# Propeller-HAT.net
KiCad netlist of a schematic drawn in EAGLE
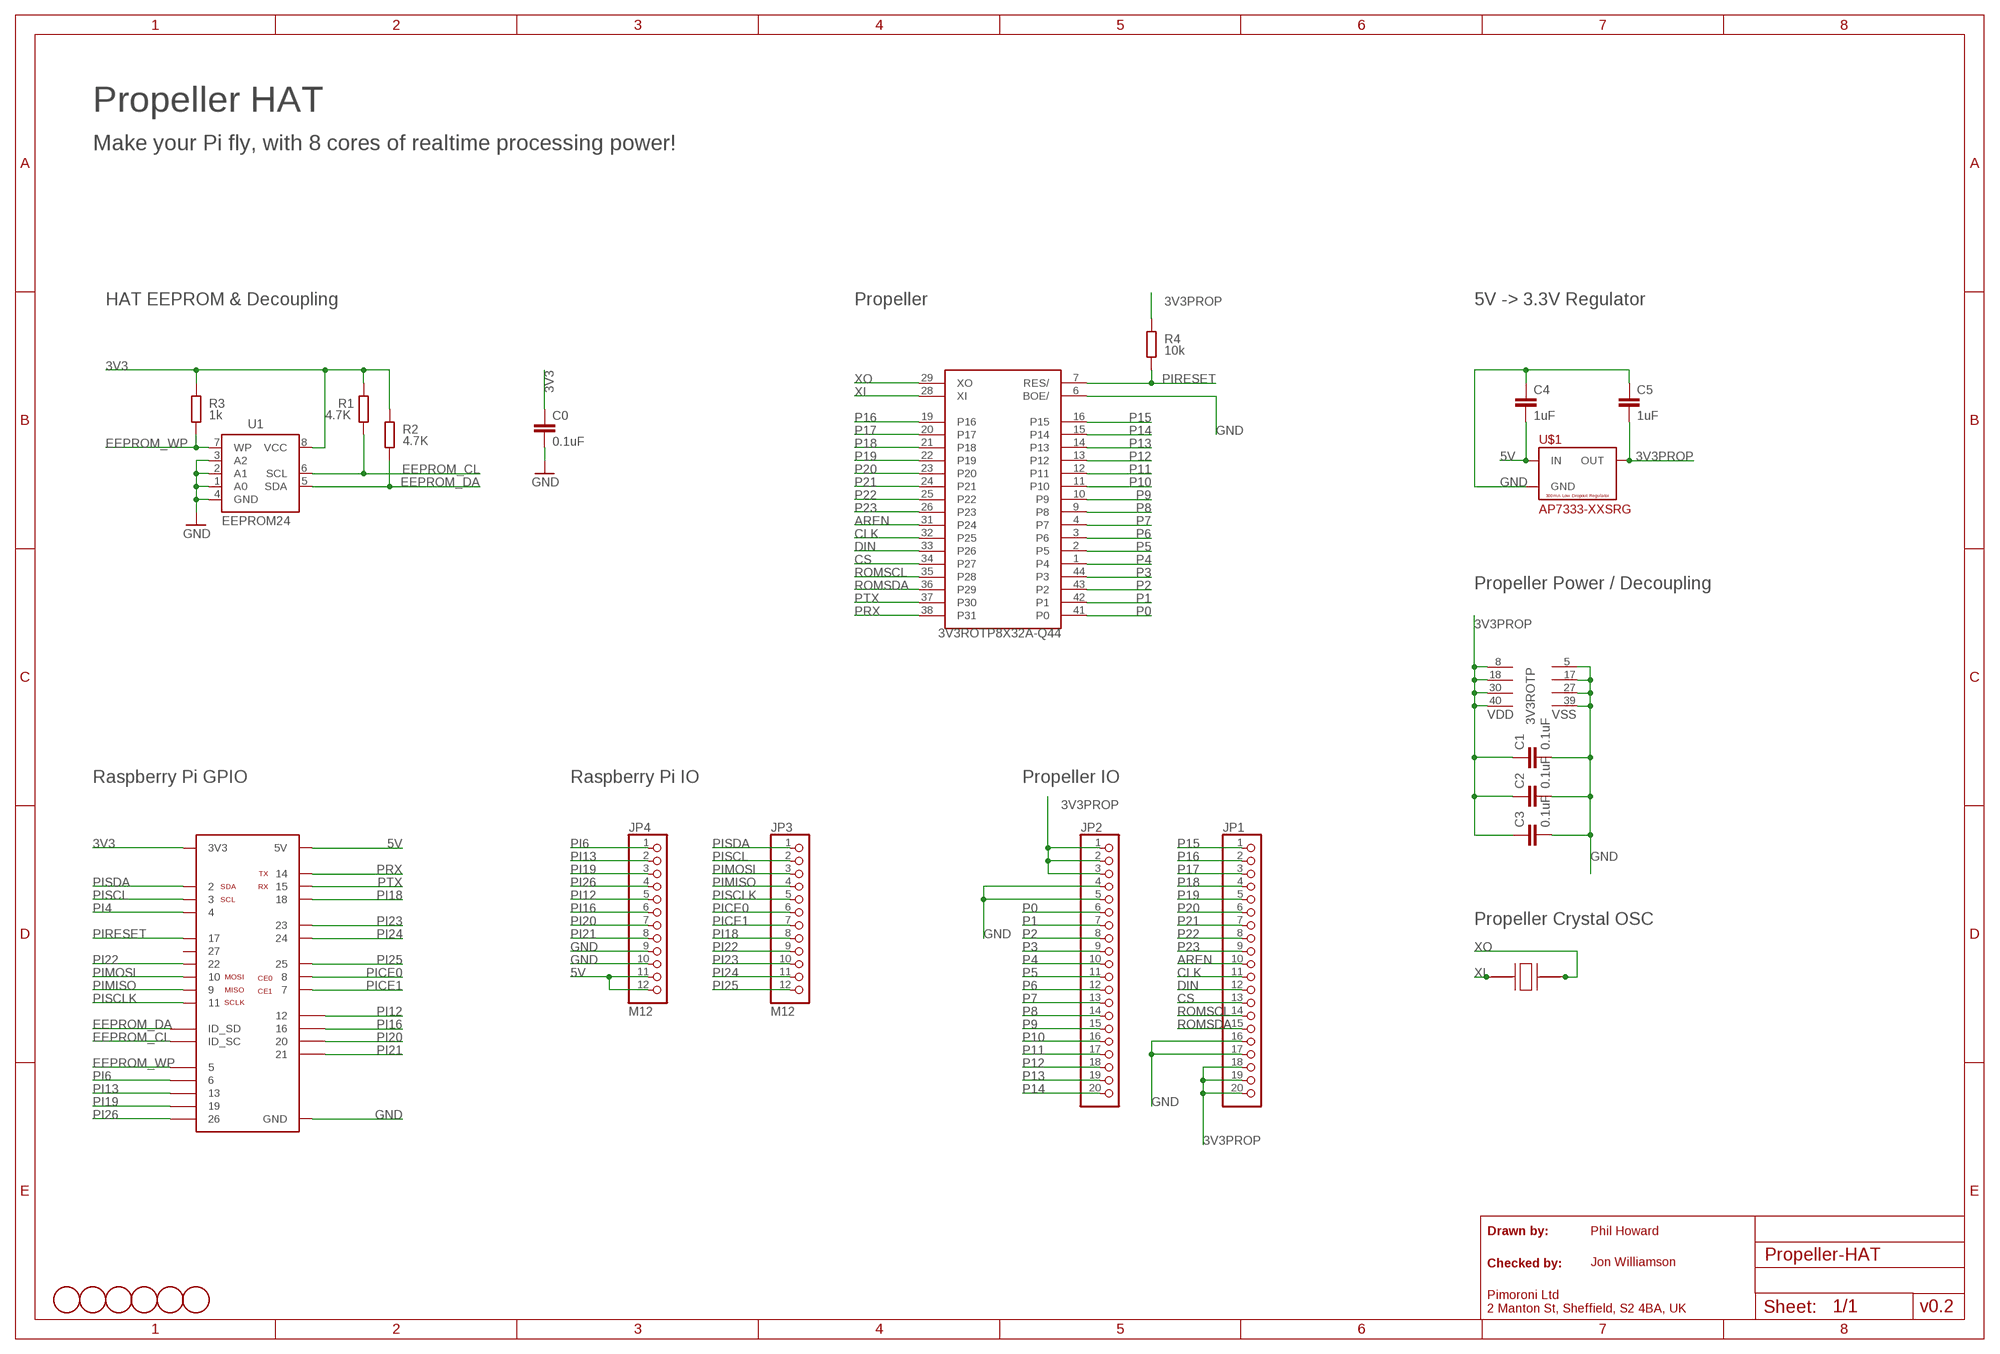
[diagram p0: schematic, sheet 1]

(export (version "E")
  (design (tool "Eeschema 10.0.6"))
  (components
    (comp (ref "3V3ROT")
      (value "P8X32A-Q44")
      (footprint "eagle-import:P8X32A-Q44")
      (libsource (lib "eagle-import") (part "P8X32A-Q44"))
    )
    (comp (ref "C0")
      (value "0.1uF")
      (footprint "eagle-import:C0603K")
      (libsource (lib "eagle-import") (part "C-EUC0603K"))
    )
    (comp (ref "C1")
      (value "0.1uF")
      (footprint "eagle-import:C0603K")
      (libsource (lib "eagle-import") (part "C-EUC0603K"))
    )
    (comp (ref "C2")
      (value "0.1uF")
      (footprint "eagle-import:C0603K")
      (libsource (lib "eagle-import") (part "C-EUC0603K"))
    )
    (comp (ref "C3")
      (value "0.1uF")
      (footprint "eagle-import:C0603K")
      (libsource (lib "eagle-import") (part "C-EUC0603K"))
    )
    (comp (ref "C4")
      (value "1uF")
      (footprint "eagle-import:C0603K")
      (libsource (lib "eagle-import") (part "C-EUC0603K"))
    )
    (comp (ref "C5")
      (value "1uF")
      (footprint "eagle-import:C0603K")
      (libsource (lib "eagle-import") (part "C-EUC0603K"))
    )
    (comp (ref "JP1")
      (value "PINHD-1X20-BIG")
      (footprint "eagle-import:1X20-BIG")
      (libsource (lib "eagle-import") (part "PINHD-1X20-BIG"))
    )
    (comp (ref "JP2")
      (value "PINHD-1X20-BIG")
      (footprint "eagle-import:1X20-BIG")
      (libsource (lib "eagle-import") (part "PINHD-1X20-BIG"))
    )
    (comp (ref "JP3")
      (value "M12")
      (footprint "eagle-import:M12")
      (libsource (lib "eagle-import") (part "M12"))
    )
    (comp (ref "JP4")
      (value "M12")
      (footprint "eagle-import:M12")
      (libsource (lib "eagle-import") (part "M12"))
    )
    (comp (ref "R1")
      (value "4.7K")
      (footprint "eagle-import:R0603")
      (fields (field (name "TOLERANCE") "5%"))
      (libsource (lib "eagle-import") (part "R-EU_R0603"))
    )
    (comp (ref "R2")
      (value "4.7K")
      (footprint "eagle-import:R0603")
      (fields (field (name "TOLERANCE") "5%"))
      (libsource (lib "eagle-import") (part "R-EU_R0603"))
    )
    (comp (ref "R3")
      (value "1k")
      (footprint "eagle-import:R0603")
      (fields (field (name "TOLERANCE") "5%"))
      (libsource (lib "eagle-import") (part "R-EU_R0603"))
    )
    (comp (ref "R4")
      (value "10k")
      (footprint "eagle-import:R0603")
      (fields (field (name "TOLERANCE") "5%"))
      (libsource (lib "eagle-import") (part "R-EU_R0603"))
    )
    (comp (ref "U$1")
      (value "AP7333-XXSRG")
      (footprint "eagle-import:SOT23")
      (libsource (lib "eagle-import") (part "AP7333-XXSRG"))
    )
    (comp (ref "U$2")
      (value "RPIGPIOPINHD-2X20-SMD-FLIPPED")
      (footprint "eagle-import:FCI_89898_313LF_40P_CONNECTOR_SMT_FLIPPED")
      (libsource (lib "eagle-import") (part "RPIGPIOPINHD-2X20-SMD-FLIPPED"))
    )
    (comp (ref "U$3")
      (value "FIDUCIAL1MM")
      (footprint "eagle-import:FIDUCIAL-1MM")
      (libsource (lib "eagle-import") (part "FIDUCIAL1MM"))
    )
    (comp (ref "U$4")
      (value "FIDUCIAL1MM")
      (footprint "eagle-import:FIDUCIAL-1MM")
      (libsource (lib "eagle-import") (part "FIDUCIAL1MM"))
    )
    (comp (ref "U$5")
      (value "FIDUCIAL1MM")
      (footprint "eagle-import:FIDUCIAL-1MM")
      (libsource (lib "eagle-import") (part "FIDUCIAL1MM"))
    )
    (comp (ref "U$6")
      (value "FIDUCIAL1MM")
      (footprint "eagle-import:FIDUCIAL-1MM")
      (libsource (lib "eagle-import") (part "FIDUCIAL1MM"))
    )
    (comp (ref "U$7")
      (value "FIDUCIAL1MM")
      (footprint "eagle-import:FIDUCIAL-1MM")
      (libsource (lib "eagle-import") (part "FIDUCIAL1MM"))
    )
    (comp (ref "U$8")
      (value "FIDUCIAL1MM")
      (footprint "eagle-import:FIDUCIAL-1MM")
      (libsource (lib "eagle-import") (part "FIDUCIAL1MM"))
    )
    (comp (ref "U$9")
      (value "ABLS3-XXXMHZ-D4Y-T")
      (footprint "eagle-import:ABLS3-XXXMHZ-D4Y-T")
      (libsource (lib "eagle-import") (part "ABLS3-XXXMHZ-D4Y-T"))
    )
    (comp (ref "U1")
      (value "EEPROM24")
      (footprint "eagle-import:SOIC8")
      (libsource (lib "eagle-import") (part "EEPROM24"))
    )
  )
  (nets
    (net (code "1") (name "/3V3") (class "Default")
      (node (ref "C0") (pin "1") (pinfunction "1_1") (pintype "passive"))
      (node (ref "R1") (pin "2") (pinfunction "2_2") (pintype "passive"))
      (node (ref "R2") (pin "2") (pinfunction "2_2") (pintype "passive"))
      (node (ref "R3") (pin "2") (pinfunction "2_2") (pintype "passive"))
      (node (ref "U$2") (pin "P17_3V3") (pinfunction "3V3_P17_3V3") (pintype "power_in"))
      (node (ref "U$2") (pin "P1_3V3") (pinfunction "3V3_P1_3V3") (pintype "power_in"))
      (node (ref "U1") (pin "8") (pinfunction "VCC_8") (pintype "power_in"))
    )
    (net (code "2") (name "/3V3PROP") (class "Default")
      (node (ref "3V3ROT") (pin "18") (pinfunction "VDD_18") (pintype "power_in"))
      (node (ref "3V3ROT") (pin "30") (pinfunction "VDD_30") (pintype "power_in"))
      (node (ref "3V3ROT") (pin "40") (pinfunction "VDD_40") (pintype "power_in"))
      (node (ref "3V3ROT") (pin "8") (pinfunction "VDD_8") (pintype "power_in"))
      (node (ref "C1") (pin "1") (pinfunction "1_1") (pintype "passive"))
      (node (ref "C2") (pin "1") (pinfunction "1_1") (pintype "passive"))
      (node (ref "C3") (pin "1") (pinfunction "1_1") (pintype "passive"))
      (node (ref "C5") (pin "2") (pinfunction "2_2") (pintype "passive"))
      (node (ref "JP1") (pin "18") (pinfunction "18_18") (pintype "passive"))
      (node (ref "JP1") (pin "19") (pinfunction "19_19") (pintype "passive"))
      (node (ref "JP1") (pin "20") (pinfunction "20_20") (pintype "passive"))
      (node (ref "JP2") (pin "1") (pinfunction "1_1") (pintype "passive"))
      (node (ref "JP2") (pin "2") (pinfunction "2_2") (pintype "passive"))
      (node (ref "JP2") (pin "3") (pinfunction "3_3") (pintype "passive"))
      (node (ref "R4") (pin "2") (pinfunction "2_2") (pintype "passive"))
      (node (ref "U$1") (pin "2") (pinfunction "OUT_2") (pintype "bidirectional"))
    )
    (net (code "3") (name "/5V") (class "Default")
      (node (ref "C4") (pin "2") (pinfunction "2_2") (pintype "passive"))
      (node (ref "JP4") (pin "11") (pinfunction "11_11") (pintype "passive"))
      (node (ref "JP4") (pin "12") (pinfunction "12_12") (pintype "passive"))
      (node (ref "U$1") (pin "3") (pinfunction "IN_3") (pintype "bidirectional"))
      (node (ref "U$2") (pin "P2_5V") (pinfunction "5V_P2_5V") (pintype "power_in"))
      (node (ref "U$2") (pin "P4_5V") (pinfunction "5V_P4_5V") (pintype "power_in"))
    )
    (net (code "4") (name "/AREN") (class "Default")
      (node (ref "3V3ROT") (pin "31") (pinfunction "P24_31") (pintype "bidirectional"))
      (node (ref "JP1") (pin "10") (pinfunction "10_10") (pintype "passive"))
    )
    (net (code "5") (name "/CLK") (class "Default")
      (node (ref "3V3ROT") (pin "32") (pinfunction "P25_32") (pintype "bidirectional"))
      (node (ref "JP1") (pin "11") (pinfunction "11_11") (pintype "passive"))
    )
    (net (code "6") (name "/CS") (class "Default")
      (node (ref "3V3ROT") (pin "34") (pinfunction "P27_34") (pintype "bidirectional"))
      (node (ref "JP1") (pin "13") (pinfunction "13_13") (pintype "passive"))
    )
    (net (code "7") (name "/DIN") (class "Default")
      (node (ref "3V3ROT") (pin "33") (pinfunction "P26_33") (pintype "bidirectional"))
      (node (ref "JP1") (pin "12") (pinfunction "12_12") (pintype "passive"))
    )
    (net (code "8") (name "/EEPROM_CL") (class "Default")
      (node (ref "R1") (pin "1") (pinfunction "1_1") (pintype "passive"))
      (node (ref "U$2") (pin "P28_IDSC") (pinfunction "ID_SC_P28_IDSC") (pintype "bidirectional"))
      (node (ref "U1") (pin "6") (pinfunction "SCL_6") (pintype "input"))
    )
    (net (code "9") (name "/EEPROM_DA") (class "Default")
      (node (ref "R2") (pin "1") (pinfunction "1_1") (pintype "passive"))
      (node (ref "U$2") (pin "P27_IDSD") (pinfunction "ID_SD_P27_IDSD") (pintype "bidirectional"))
      (node (ref "U1") (pin "5") (pinfunction "SDA_5") (pintype "bidirectional"))
    )
    (net (code "10") (name "/EEPROM_WP") (class "Default")
      (node (ref "R3") (pin "1") (pinfunction "1_1") (pintype "passive"))
      (node (ref "U$2") (pin "P29_GPIO5") (pinfunction "5_P29_GPIO5") (pintype "bidirectional"))
      (node (ref "U1") (pin "7") (pinfunction "WP_7") (pintype "input"))
    )
    (net (code "11") (name "/P0") (class "Default")
      (node (ref "3V3ROT") (pin "41") (pinfunction "P0_41") (pintype "bidirectional"))
      (node (ref "JP2") (pin "6") (pinfunction "6_6") (pintype "passive"))
    )
    (net (code "12") (name "/P1") (class "Default")
      (node (ref "3V3ROT") (pin "42") (pinfunction "P1_42") (pintype "bidirectional"))
      (node (ref "JP2") (pin "7") (pinfunction "7_7") (pintype "passive"))
    )
    (net (code "13") (name "/P2") (class "Default")
      (node (ref "3V3ROT") (pin "43") (pinfunction "P2_43") (pintype "bidirectional"))
      (node (ref "JP2") (pin "8") (pinfunction "8_8") (pintype "passive"))
    )
    (net (code "14") (name "/P3") (class "Default")
      (node (ref "3V3ROT") (pin "44") (pinfunction "P3_44") (pintype "bidirectional"))
      (node (ref "JP2") (pin "9") (pinfunction "9_9") (pintype "passive"))
    )
    (net (code "15") (name "/P4") (class "Default")
      (node (ref "3V3ROT") (pin "1") (pinfunction "P4_1") (pintype "bidirectional"))
      (node (ref "JP2") (pin "10") (pinfunction "10_10") (pintype "passive"))
    )
    (net (code "16") (name "/P5") (class "Default")
      (node (ref "3V3ROT") (pin "2") (pinfunction "P5_2") (pintype "bidirectional"))
      (node (ref "JP2") (pin "11") (pinfunction "11_11") (pintype "passive"))
    )
    (net (code "17") (name "/P6") (class "Default")
      (node (ref "3V3ROT") (pin "3") (pinfunction "P6_3") (pintype "bidirectional"))
      (node (ref "JP2") (pin "12") (pinfunction "12_12") (pintype "passive"))
    )
    (net (code "18") (name "/P7") (class "Default")
      (node (ref "3V3ROT") (pin "4") (pinfunction "P7_4") (pintype "bidirectional"))
      (node (ref "JP2") (pin "13") (pinfunction "13_13") (pintype "passive"))
    )
    (net (code "19") (name "/P8") (class "Default")
      (node (ref "3V3ROT") (pin "9") (pinfunction "P8_9") (pintype "bidirectional"))
      (node (ref "JP2") (pin "14") (pinfunction "14_14") (pintype "passive"))
    )
    (net (code "20") (name "/P9") (class "Default")
      (node (ref "3V3ROT") (pin "10") (pinfunction "P9_10") (pintype "bidirectional"))
      (node (ref "JP2") (pin "15") (pinfunction "15_15") (pintype "passive"))
    )
    (net (code "21") (name "/P10") (class "Default")
      (node (ref "3V3ROT") (pin "11") (pinfunction "P10_11") (pintype "bidirectional"))
      (node (ref "JP2") (pin "16") (pinfunction "16_16") (pintype "passive"))
    )
    (net (code "22") (name "/P11") (class "Default")
      (node (ref "3V3ROT") (pin "12") (pinfunction "P11_12") (pintype "bidirectional"))
      (node (ref "JP2") (pin "17") (pinfunction "17_17") (pintype "passive"))
    )
    (net (code "23") (name "/P12") (class "Default")
      (node (ref "3V3ROT") (pin "13") (pinfunction "P12_13") (pintype "bidirectional"))
      (node (ref "JP2") (pin "18") (pinfunction "18_18") (pintype "passive"))
    )
    (net (code "24") (name "/P13") (class "Default")
      (node (ref "3V3ROT") (pin "14") (pinfunction "P13_14") (pintype "bidirectional"))
      (node (ref "JP2") (pin "19") (pinfunction "19_19") (pintype "passive"))
    )
    (net (code "25") (name "/P14") (class "Default")
      (node (ref "3V3ROT") (pin "15") (pinfunction "P14_15") (pintype "bidirectional"))
      (node (ref "JP2") (pin "20") (pinfunction "20_20") (pintype "passive"))
    )
    (net (code "26") (name "/P15") (class "Default")
      (node (ref "3V3ROT") (pin "16") (pinfunction "P15_16") (pintype "bidirectional"))
      (node (ref "JP1") (pin "1") (pinfunction "1_1") (pintype "passive"))
    )
    (net (code "27") (name "/P16") (class "Default")
      (node (ref "3V3ROT") (pin "19") (pinfunction "P16_19") (pintype "bidirectional"))
      (node (ref "JP1") (pin "2") (pinfunction "2_2") (pintype "passive"))
    )
    (net (code "28") (name "/P17") (class "Default")
      (node (ref "3V3ROT") (pin "20") (pinfunction "P17_20") (pintype "bidirectional"))
      (node (ref "JP1") (pin "3") (pinfunction "3_3") (pintype "passive"))
    )
    (net (code "29") (name "/P18") (class "Default")
      (node (ref "3V3ROT") (pin "21") (pinfunction "P18_21") (pintype "bidirectional"))
      (node (ref "JP1") (pin "4") (pinfunction "4_4") (pintype "passive"))
    )
    (net (code "30") (name "/P19") (class "Default")
      (node (ref "3V3ROT") (pin "22") (pinfunction "P19_22") (pintype "bidirectional"))
      (node (ref "JP1") (pin "5") (pinfunction "5_5") (pintype "passive"))
    )
    (net (code "31") (name "/P20") (class "Default")
      (node (ref "3V3ROT") (pin "23") (pinfunction "P20_23") (pintype "bidirectional"))
      (node (ref "JP1") (pin "6") (pinfunction "6_6") (pintype "passive"))
    )
    (net (code "32") (name "/P21") (class "Default")
      (node (ref "3V3ROT") (pin "24") (pinfunction "P21_24") (pintype "bidirectional"))
      (node (ref "JP1") (pin "7") (pinfunction "7_7") (pintype "passive"))
    )
    (net (code "33") (name "/P22") (class "Default")
      (node (ref "3V3ROT") (pin "25") (pinfunction "P22_25") (pintype "bidirectional"))
      (node (ref "JP1") (pin "8") (pinfunction "8_8") (pintype "passive"))
    )
    (net (code "34") (name "/P23") (class "Default")
      (node (ref "3V3ROT") (pin "26") (pinfunction "P23_26") (pintype "bidirectional"))
      (node (ref "JP1") (pin "9") (pinfunction "9_9") (pintype "passive"))
    )
    (net (code "35") (name "/PI4") (class "Default")
      (node (ref "U$2") (pin "P7_GPIO4") (pinfunction "4_P7_GPIO4") (pintype "bidirectional"))
    )
    (net (code "36") (name "/PI6") (class "Default")
      (node (ref "JP4") (pin "1") (pinfunction "1_1") (pintype "passive"))
      (node (ref "U$2") (pin "P31_GPIO6") (pinfunction "6_P31_GPIO6") (pintype "bidirectional"))
    )
    (net (code "37") (name "/PI12") (class "Default")
      (node (ref "JP4") (pin "5") (pinfunction "5_5") (pintype "passive"))
      (node (ref "U$2") (pin "P32_GPIO12") (pinfunction "12_P32_GPIO12") (pintype "bidirectional"))
    )
    (net (code "38") (name "/PI13") (class "Default")
      (node (ref "JP4") (pin "2") (pinfunction "2_2") (pintype "passive"))
      (node (ref "U$2") (pin "P33_GPIO13") (pinfunction "13_P33_GPIO13") (pintype "bidirectional"))
    )
    (net (code "39") (name "/PI16") (class "Default")
      (node (ref "JP4") (pin "6") (pinfunction "6_6") (pintype "passive"))
      (node (ref "U$2") (pin "P36_GPIO16") (pinfunction "16_P36_GPIO16") (pintype "bidirectional"))
    )
    (net (code "40") (name "/PI18") (class "Default")
      (node (ref "JP3") (pin "8") (pinfunction "8_8") (pintype "passive"))
      (node (ref "U$2") (pin "P12_GPIO18") (pinfunction "18_P12_GPIO18") (pintype "bidirectional"))
    )
    (net (code "41") (name "/PI19") (class "Default")
      (node (ref "JP4") (pin "3") (pinfunction "3_3") (pintype "passive"))
      (node (ref "U$2") (pin "P35_GPIO19") (pinfunction "19_P35_GPIO19") (pintype "bidirectional"))
    )
    (net (code "42") (name "/PI20") (class "Default")
      (node (ref "JP4") (pin "7") (pinfunction "7_7") (pintype "passive"))
      (node (ref "U$2") (pin "P38_GPIO20") (pinfunction "20_P38_GPIO20") (pintype "bidirectional"))
    )
    (net (code "43") (name "/PI21") (class "Default")
      (node (ref "JP4") (pin "8") (pinfunction "8_8") (pintype "passive"))
      (node (ref "U$2") (pin "P40_GPIO21") (pinfunction "21_P40_GPIO21") (pintype "bidirectional"))
    )
    (net (code "44") (name "/PI22") (class "Default")
      (node (ref "JP3") (pin "9") (pinfunction "9_9") (pintype "passive"))
      (node (ref "U$2") (pin "P15_GPIO22") (pinfunction "22_P15_GPIO22") (pintype "bidirectional"))
    )
    (net (code "45") (name "/PI23") (class "Default")
      (node (ref "JP3") (pin "10") (pinfunction "10_10") (pintype "passive"))
      (node (ref "U$2") (pin "P16_GPIO23") (pinfunction "23_P16_GPIO23") (pintype "bidirectional"))
    )
    (net (code "46") (name "/PI24") (class "Default")
      (node (ref "JP3") (pin "11") (pinfunction "11_11") (pintype "passive"))
      (node (ref "U$2") (pin "P18_GPIO24") (pinfunction "24_P18_GPIO24") (pintype "bidirectional"))
    )
    (net (code "47") (name "/PI25") (class "Default")
      (node (ref "JP3") (pin "12") (pinfunction "12_12") (pintype "passive"))
      (node (ref "U$2") (pin "P22_GPIO25") (pinfunction "25_P22_GPIO25") (pintype "bidirectional"))
    )
    (net (code "48") (name "/PI26") (class "Default")
      (node (ref "JP4") (pin "4") (pinfunction "4_4") (pintype "passive"))
      (node (ref "U$2") (pin "P37_GPIO26") (pinfunction "26_P37_GPIO26") (pintype "bidirectional"))
    )
    (net (code "49") (name "/PICE0") (class "Default")
      (node (ref "JP3") (pin "6") (pinfunction "6_6") (pintype "passive"))
      (node (ref "U$2") (pin "P24_GPIO8_SPI0_CE0") (pinfunction "8_P24_GPIO8_SPI0_CE0") (pintype "bidirectional"))
    )
    (net (code "50") (name "/PICE1") (class "Default")
      (node (ref "JP3") (pin "7") (pinfunction "7_7") (pintype "passive"))
      (node (ref "U$2") (pin "P26_GPIO7_SPI0_CE1") (pinfunction "7_P26_GPIO7_SPI0_CE1") (pintype "bidirectional"))
    )
    (net (code "51") (name "/PIMISO") (class "Default")
      (node (ref "JP3") (pin "4") (pinfunction "4_4") (pintype "passive"))
      (node (ref "U$2") (pin "P21_GPIO9_SPI0_MISO") (pinfunction "9_P21_GPIO9_SPI0_MISO") (pintype "bidirectional"))
    )
    (net (code "52") (name "/PIMOSI") (class "Default")
      (node (ref "JP3") (pin "3") (pinfunction "3_3") (pintype "passive"))
      (node (ref "U$2") (pin "P19_GPIO10_SPI0_MOSI") (pinfunction "10_P19_GPIO10_SPI0_MOSI") (pintype "bidirectional"))
    )
    (net (code "53") (name "/PIRESET") (class "Default")
      (node (ref "3V3ROT") (pin "7") (pinfunction "RES/_7") (pintype "bidirectional"))
      (node (ref "R4") (pin "1") (pinfunction "1_1") (pintype "passive"))
      (node (ref "U$2") (pin "P11_GPIO17") (pinfunction "17_P11_GPIO17") (pintype "bidirectional"))
    )
    (net (code "54") (name "/PISCL") (class "Default")
      (node (ref "JP3") (pin "2") (pinfunction "2_2") (pintype "passive"))
      (node (ref "U$2") (pin "P5_GPIO3_SCL") (pinfunction "3_P5_GPIO3_SCL") (pintype "bidirectional"))
    )
    (net (code "55") (name "/PISCLK") (class "Default")
      (node (ref "JP3") (pin "5") (pinfunction "5_5") (pintype "passive"))
      (node (ref "U$2") (pin "P23_GPIO11_SPI0_SCLK") (pinfunction "11_P23_GPIO11_SPI0_SCLK") (pintype "bidirectional"))
    )
    (net (code "56") (name "/PISDA") (class "Default")
      (node (ref "JP3") (pin "1") (pinfunction "1_1") (pintype "passive"))
      (node (ref "U$2") (pin "P3_GPIO2_SDA") (pinfunction "2_P3_GPIO2_SDA") (pintype "bidirectional"))
    )
    (net (code "57") (name "/PRX") (class "Default")
      (node (ref "3V3ROT") (pin "38") (pinfunction "P31_38") (pintype "bidirectional"))
      (node (ref "U$2") (pin "P8_GPIO14_UART0_TXD") (pinfunction "14_P8_GPIO14_UART0_TXD") (pintype "bidirectional"))
    )
    (net (code "58") (name "/PTX") (class "Default")
      (node (ref "3V3ROT") (pin "37") (pinfunction "P30_37") (pintype "bidirectional"))
      (node (ref "U$2") (pin "P10_GPIO15_UART0_RXD") (pinfunction "15_P10_GPIO15_UART0_RXD") (pintype "bidirectional"))
    )
    (net (code "59") (name "/ROMSCL") (class "Default")
      (node (ref "3V3ROT") (pin "35") (pinfunction "P28_35") (pintype "bidirectional"))
      (node (ref "JP1") (pin "14") (pinfunction "14_14") (pintype "passive"))
    )
    (net (code "60") (name "/ROMSDA") (class "Default")
      (node (ref "3V3ROT") (pin "36") (pinfunction "P29_36") (pintype "bidirectional"))
      (node (ref "JP1") (pin "15") (pinfunction "15_15") (pintype "passive"))
    )
    (net (code "61") (name "/XI") (class "Default")
      (node (ref "3V3ROT") (pin "28") (pinfunction "XI_28") (pintype "input"))
      (node (ref "U$9") (pin "P$1") (pinfunction "1_P$1") (pintype "bidirectional"))
    )
    (net (code "62") (name "/XO") (class "Default")
      (node (ref "3V3ROT") (pin "29") (pinfunction "XO_29") (pintype "output"))
      (node (ref "U$9") (pin "P$2") (pinfunction "3_P$2") (pintype "bidirectional"))
    )
    (net (code "63") (name "GND") (class "Default")
      (node (ref "3V3ROT") (pin "17") (pinfunction "VSS_17") (pintype "power_in"))
      (node (ref "3V3ROT") (pin "27") (pinfunction "VSS_27") (pintype "power_in"))
      (node (ref "3V3ROT") (pin "39") (pinfunction "VSS_39") (pintype "power_in"))
      (node (ref "3V3ROT") (pin "5") (pinfunction "VSS_5") (pintype "power_in"))
      (node (ref "3V3ROT") (pin "6") (pinfunction "BOE/_6") (pintype "input"))
      (node (ref "C0") (pin "2") (pinfunction "2_2") (pintype "passive"))
      (node (ref "C1") (pin "2") (pinfunction "2_2") (pintype "passive"))
      (node (ref "C2") (pin "2") (pinfunction "2_2") (pintype "passive"))
      (node (ref "C3") (pin "2") (pinfunction "2_2") (pintype "passive"))
      (node (ref "C4") (pin "1") (pinfunction "1_1") (pintype "passive"))
      (node (ref "C5") (pin "1") (pinfunction "1_1") (pintype "passive"))
      (node (ref "JP1") (pin "16") (pinfunction "16_16") (pintype "passive"))
      (node (ref "JP1") (pin "17") (pinfunction "17_17") (pintype "passive"))
      (node (ref "JP2") (pin "4") (pinfunction "4_4") (pintype "passive"))
      (node (ref "JP2") (pin "5") (pinfunction "5_5") (pintype "passive"))
      (node (ref "JP4") (pin "10") (pinfunction "10_10") (pintype "passive"))
      (node (ref "JP4") (pin "9") (pinfunction "9_9") (pintype "passive"))
      (node (ref "U$1") (pin "1") (pinfunction "GND_1") (pintype "bidirectional"))
      (node (ref "U$2") (pin "P14_GND") (pinfunction "GND_P14_GND") (pintype "passive"))
      (node (ref "U$2") (pin "P20_GND") (pinfunction "GND_P20_GND") (pintype "passive"))
      (node (ref "U$2") (pin "P25_GND") (pinfunction "GND_P25_GND") (pintype "passive"))
      (node (ref "U$2") (pin "P30_GND") (pinfunction "GND_P30_GND") (pintype "passive"))
      (node (ref "U$2") (pin "P34_GND") (pinfunction "GND_P34_GND") (pintype "passive"))
      (node (ref "U$2") (pin "P39_GND") (pinfunction "GND_P39_GND") (pintype "passive"))
      (node (ref "U$2") (pin "P6_GND") (pinfunction "GND_P6_GND") (pintype "passive"))
      (node (ref "U$2") (pin "P9_GND") (pinfunction "GND_P9_GND") (pintype "passive"))
      (node (ref "U1") (pin "1") (pinfunction "A0_1") (pintype "input"))
      (node (ref "U1") (pin "2") (pinfunction "A1_2") (pintype "input"))
      (node (ref "U1") (pin "3") (pinfunction "A2_3") (pintype "input"))
      (node (ref "U1") (pin "4") (pinfunction "GND_4") (pintype "power_in"))
    )
    (net (code "64") (name "unconnected-(U$2-27-PadP13_GPIO27)") (class "Default")
      (node (ref "U$2") (pin "P13_GPIO27") (pinfunction "27_P13_GPIO27") (pintype "bidirectional"))
    )
  )
)
